# 03_-_SUMOBOT.net
KiCad netlist of a schematic drawn in Altium Designer
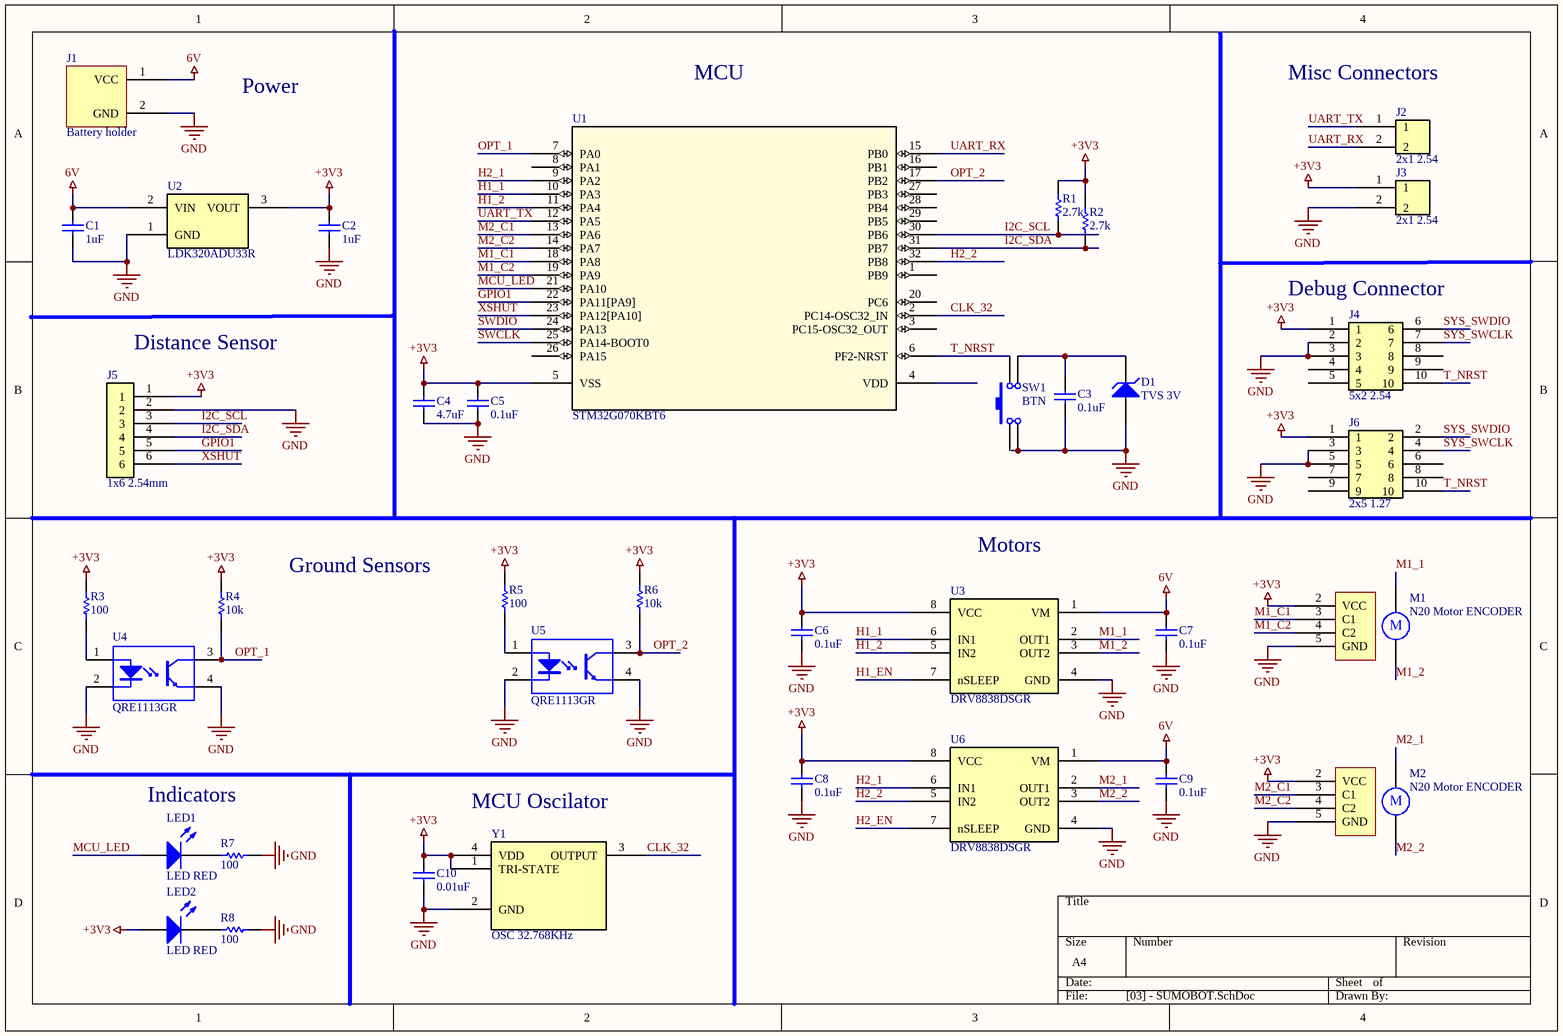
[diagram p0: [03] - SUMOBOT.SchDoc]

(export (version "E")
  (design (tool "Eeschema 10.0.6"))
  (components
    (comp (ref "C1")
      (value "1uF")
      (footprint "CAPC2012X14N")
      (fields
        (field (name "MANUFACTURER") "Samsung")
        (field (name "MANUFACTURER PART NUMBER") "CL21B105KOFNNNG")
        (field (name "TOLERANCE") "10%")
      )
      (libsource (lib "Sumobot2kl20") (part "CL21B105KOFNNNG"))
    )
    (comp (ref "C2")
      (value "1uF")
      (footprint "CAPC2012X14N")
      (fields
        (field (name "MANUFACTURER") "Samsung")
        (field (name "MANUFACTURER PART NUMBER") "CL21B105KOFNNNG")
        (field (name "TOLERANCE") "10%")
      )
      (libsource (lib "Sumobot2kl20") (part "CL21B105KOFNNNG"))
    )
    (comp (ref "C3")
      (value "0.1uF")
      (footprint "CAPC2012X14N")
      (description "CAP CER 0.1UF 50V Y5V 0805")
      (fields
        (field (name "MANUFACTURER") "Samsung")
        (field (name "MANUFACTURER PART NUMBER") "CL21F104ZBCNNNC")
      )
      (libsource (lib "Sumobot2kl20") (part "CL21F104ZBCNNNC"))
    )
    (comp (ref "C4")
      (value "4.7uF")
      (footprint "CAPC2012X14N")
      (fields
        (field (name "MANUFACTURER") "Samsung")
        (field (name "MANUFACTURER PART NUMBER") "CL21B475KOFNNNE")
        (field (name "TOLERANCE") "10%")
      )
      (libsource (lib "Sumobot2kl20") (part "CL21B475KOFNNNE"))
    )
    (comp (ref "C5")
      (value "0.1uF")
      (footprint "CAPC2012X14N")
      (description "CAP CER 0.1UF 50V Y5V 0805")
      (fields
        (field (name "MANUFACTURER") "Samsung")
        (field (name "MANUFACTURER PART NUMBER") "CL21F104ZBCNNNC")
      )
      (libsource (lib "Sumobot2kl20") (part "CL21F104ZBCNNNC"))
    )
    (comp (ref "C6")
      (value "0.1uF")
      (footprint "CAPC2012X14N")
      (description "CAP CER 0.1UF 50V Y5V 0805")
      (fields
        (field (name "MANUFACTURER") "Samsung")
        (field (name "MANUFACTURER PART NUMBER") "CL21F104ZBCNNNC")
      )
      (libsource (lib "Sumobot2kl20") (part "CL21F104ZBCNNNC"))
    )
    (comp (ref "C7")
      (value "0.1uF")
      (footprint "CAPC2012X14N")
      (description "CAP CER 0.1UF 50V Y5V 0805")
      (fields
        (field (name "MANUFACTURER") "Samsung")
        (field (name "MANUFACTURER PART NUMBER") "CL21F104ZBCNNNC")
      )
      (libsource (lib "Sumobot2kl20") (part "CL21F104ZBCNNNC"))
    )
    (comp (ref "C8")
      (value "0.1uF")
      (footprint "CAPC2012X14N")
      (description "CAP CER 0.1UF 50V Y5V 0805")
      (fields
        (field (name "MANUFACTURER") "Samsung")
        (field (name "MANUFACTURER PART NUMBER") "CL21F104ZBCNNNC")
      )
      (libsource (lib "Sumobot2kl20") (part "CL21F104ZBCNNNC"))
    )
    (comp (ref "C9")
      (value "0.1uF")
      (footprint "CAPC2012X14N")
      (description "CAP CER 0.1UF 50V Y5V 0805")
      (fields
        (field (name "MANUFACTURER") "Samsung")
        (field (name "MANUFACTURER PART NUMBER") "CL21F104ZBCNNNC")
      )
      (libsource (lib "Sumobot2kl20") (part "CL21F104ZBCNNNC"))
    )
    (comp (ref "C10")
      (value "0.01uF")
      (footprint "CAPC2012X14N")
      (fields
        (field (name "MANUFACTURER") "Samsung")
        (field (name "MANUFACTURER PART NUMBER") "CL21B103KBANNNC")
        (field (name "TOLERANCE") "10%")
      )
      (libsource (lib "Sumobot2kl20") (part "CL21B103KBANNNC"))
    )
    (comp (ref "D1")
      (value "TVS 3V")
      (footprint "ST0201")
      (description "ESD Suppressor TVS 8KV 2-Pin SMD T/R")
      (fields
        (field (name "MANUFACTURER") "STMicroelectronics")
        (field (name "MANUFACTURER PART NUMBER") "ESDALC6V1-1U2")
      )
      (libsource (lib "Sumobot2kl20") (part "ESDALC6V1-1U2"))
    )
    (comp (ref "J1")
      (value "Battery holder")
      (footprint "Battery Holder")
      (libsource (lib "Sumobot2kl20") (part "Battery holder"))
    )
    (comp (ref "J2")
      (value "2x1 2.54")
      (footprint "2 2.54")
      (description "CONN HEADER VERT 2POS 2.54MM")
      (fields
        (field (name "MANUFACTURER") "Sullins")
        (field (name "MANUFACTURER PART NUMBER") "PREC002SAAN-RC")
      )
      (libsource (lib "Sumobot2kl20") (part "PREC002SAAN-RC"))
    )
    (comp (ref "J3")
      (value "2x1 2.54")
      (footprint "2 2.54")
      (description "CONN HEADER VERT 2POS 2.54MM")
      (fields
        (field (name "MANUFACTURER") "Sullins")
        (field (name "MANUFACTURER PART NUMBER") "PREC002SAAN-RC")
      )
      (libsource (lib "Sumobot2kl20") (part "PREC002SAAN-RC"))
    )
    (comp (ref "J4")
      (value "5x2 2.54")
      (footprint "5x2 2.54")
      (description "Conn Unshrouded Header HDR 80 POS 2.54mm Solder RA Thru-Hole Bag")
      (fields
        (field (name "MANUFACTURER") "Adam Equipment")
        (field (name "MANUFACTURER PART NUMBER") "PH2-10-UA")
      )
      (libsource (lib "Sumobot2kl20") (part "PH2-10-UA"))
    )
    (comp (ref "J5")
      (value "1x6 2.54mm")
      (footprint "PIN 6x1 2.54mm")
      (description "Conn Unshrouded Header HDR 6 POS 2.54mm Solder RA Thru-Hole")
      (fields
        (field (name "MANUFACTURER") "Adam Equipment")
        (field (name "MANUFACTURER PART NUMBER") "PH1RA-06-UA")
      )
      (libsource (lib "Sumobot2kl20") (part "PH1RA-06-UA"))
    )
    (comp (ref "J6")
      (value "2x5 1.27")
      (footprint "5x2 1.27")
      (description "CONN HEADER VERT 10POS 1.27MM")
      (fields
        (field (name "MANUFACTURER") "CNC Tech")
        (field (name "MANUFACTURER PART NUMBER") "3220-10-0100-00")
      )
      (libsource (lib "Sumobot2kl20") (part "3220-10-0100-00"))
    )
    (comp (ref "LED1")
      (value "LED RED")
      (footprint "LED 0805")
      (description "SMD LED red 2.4 V 0805, 150080RS75000, Würth Elektronik")
      (fields
        (field (name "MANUFACTURER") "Wurth Electronics")
        (field (name "MANUFACTURER PART NUMBER") "150080RS75000")
      )
      (libsource (lib "Sumobot2kl20") (part "150080RS75000"))
    )
    (comp (ref "LED2")
      (value "LED RED")
      (footprint "LED 0805")
      (description "SMD LED red 2.4 V 0805, 150080RS75000, Würth Elektronik")
      (fields
        (field (name "MANUFACTURER") "Wurth Electronics")
        (field (name "MANUFACTURER PART NUMBER") "150080RS75000")
      )
      (libsource (lib "Sumobot2kl20") (part "150080RS75000"))
    )
    (comp (ref "M1")
      (value "N20 Motor ENCODER")
      (footprint "N20 MOTOR - ENCODER")
      (libsource (lib "Sumobot2kl20") (part "N20 Motor ENCODER"))
    )
    (comp (ref "M2")
      (value "N20 Motor ENCODER")
      (footprint "N20 MOTOR - ENCODER")
      (libsource (lib "Sumobot2kl20") (part "N20 Motor ENCODER"))
    )
    (comp (ref "R1")
      (value "2.7k")
      (footprint "RESC2012X07N")
      (description "Res Thick Film 0805 2.7K Ohm 1% 0.125W(1/8W) ±100ppm/C Pad SMD Automotive T/R")
      (fields
        (field (name "MANUFACTURER") "Panasonic")
        (field (name "MANUFACTURER PART NUMBER") "ERJ-6ENF2701V")
      )
      (libsource (lib "Sumobot2kl20") (part "ERJ-6ENF2701V"))
    )
    (comp (ref "R2")
      (value "2.7k")
      (footprint "RESC2012X07N")
      (description "Res Thick Film 0805 2.7K Ohm 1% 0.125W(1/8W) ±100ppm/C Pad SMD Automotive T/R")
      (fields
        (field (name "MANUFACTURER") "Panasonic")
        (field (name "MANUFACTURER PART NUMBER") "ERJ-6ENF2701V")
      )
      (libsource (lib "Sumobot2kl20") (part "ERJ-6ENF2701V"))
    )
    (comp (ref "R3")
      (value "100")
      (footprint "RESC2012X07N")
      (description "PANASONIC - ERJ6ENF1000V - DICKSCH.WIDERSTAND 100R 1% 0.125W 0805")
      (fields
        (field (name "MANUFACTURER") "Panasonic")
        (field (name "MANUFACTURER PART NUMBER") "ERJ-6ENF1000V")
      )
      (libsource (lib "Sumobot2kl20") (part "ERJ-6ENF1000V"))
    )
    (comp (ref "R4")
      (value "10k")
      (footprint "RESC2012X07N")
      (fields
        (field (name "MANUFACTURER") "Panasonic")
        (field (name "MANUFACTURER PART NUMBER") "ERJ-6ENF1002V")
        (field (name "TOLERANCE") "1%")
      )
      (libsource (lib "Sumobot2kl20") (part "ERJ-6ENF1002V"))
    )
    (comp (ref "R5")
      (value "100")
      (footprint "RESC2012X07N")
      (description "PANASONIC - ERJ6ENF1000V - DICKSCH.WIDERSTAND 100R 1% 0.125W 0805")
      (fields
        (field (name "MANUFACTURER") "Panasonic")
        (field (name "MANUFACTURER PART NUMBER") "ERJ-6ENF1000V")
      )
      (libsource (lib "Sumobot2kl20") (part "ERJ-6ENF1000V"))
    )
    (comp (ref "R6")
      (value "10k")
      (footprint "RESC2012X07N")
      (fields
        (field (name "MANUFACTURER") "Panasonic")
        (field (name "MANUFACTURER PART NUMBER") "ERJ-6ENF1002V")
        (field (name "TOLERANCE") "1%")
      )
      (libsource (lib "Sumobot2kl20") (part "ERJ-6ENF1002V"))
    )
    (comp (ref "R7")
      (value "100")
      (footprint "RESC2012X07N")
      (description "PANASONIC - ERJ6ENF1000V - DICKSCH.WIDERSTAND 100R 1% 0.125W 0805")
      (fields
        (field (name "MANUFACTURER") "Panasonic")
        (field (name "MANUFACTURER PART NUMBER") "ERJ-6ENF1000V")
      )
      (libsource (lib "Sumobot2kl20") (part "ERJ-6ENF1000V"))
    )
    (comp (ref "R8")
      (value "100")
      (footprint "RESC2012X07N")
      (description "PANASONIC - ERJ6ENF1000V - DICKSCH.WIDERSTAND 100R 1% 0.125W 0805")
      (fields
        (field (name "MANUFACTURER") "Panasonic")
        (field (name "MANUFACTURER PART NUMBER") "ERJ-6ENF1000V")
      )
      (libsource (lib "Sumobot2kl20") (part "ERJ-6ENF1000V"))
    )
    (comp (ref "SW1")
      (value "BTN")
      (footprint "Button")
      (description "INWALL LENS COVER , WHITE , 6 (")
      (fields
        (field (name "MANUFACTURER") "ITT C&K")
        (field (name "MANUFACTURER PART NUMBER") "PTS647SK70SMTR2LFS")
      )
      (libsource (lib "Sumobot2kl20") (part "PTS647SK70SMTR2LFS"))
    )
    (comp (ref "U1")
      (value "STM32G070KBT6")
      (footprint "LQFP-32")
      (description "Cortex M0+ 128K LQFP32 85°C")
      (fields (field (name "MANUFACTURER") "STMicroelectronics"))
      (libsource (lib "Sumobot2kl20") (part "STM32G070KBT6"))
    )
    (comp (ref "U2")
      (value "LDK320ADU33R")
      (footprint "SOT89-150P349X160-3N")
      (description "LDO Regulator Pos 3.3V 0.2A 4-Pin(3+Tab) SOT-89 T/R")
      (fields (field (name "MANUFACTURER") "STMicroelectronics"))
      (libsource (lib "Sumobot2kl20") (part "LDK320ADU33R"))
    )
    (comp (ref "U3")
      (value "DRV8838DSGR")
      (footprint "SON50P200X80_HS-9N2")
      (fields (field (name "MANUFACTURER") "Texas Instruments"))
      (libsource (lib "Sumobot2kl20") (part "DRV8838DSGR"))
    )
    (comp (ref "U4")
      (value "QRE1113GR")
      (footprint "FAIR-QRE1113GR_V")
      (description "Photointerrupter Reflective Phototransistor 4-Pin Miniature SMT T/R")
      (fields (field (name "MANUFACTURER") "ON Semiconductor / Fairchild"))
      (libsource (lib "Sumobot2kl20") (part "QRE1113GR"))
    )
    (comp (ref "U5")
      (value "QRE1113GR")
      (footprint "FAIR-QRE1113GR_V")
      (description "Photointerrupter Reflective Phototransistor 4-Pin Miniature SMT T/R")
      (fields (field (name "MANUFACTURER") "ON Semiconductor / Fairchild"))
      (libsource (lib "Sumobot2kl20") (part "QRE1113GR"))
    )
    (comp (ref "U6")
      (value "DRV8838DSGR")
      (footprint "SON50P200X80_HS-9N2")
      (fields (field (name "MANUFACTURER") "Texas Instruments"))
      (libsource (lib "Sumobot2kl20") (part "DRV8838DSGR"))
    )
    (comp (ref "Y1")
      (value "OSC 32.768KHz")
      (footprint "ECS-327MVATX")
      (description "Oscillator XO 0.032768MHz ±25ppm 15pF CMOS 55% 1.8V/2.5V/3.3V 4-Pin Mini-SMD T/R")
      (fields
        (field (name "MANUFACTURER") "ECS International")
        (field (name "MANUFACTURER PART NUMBER") "ECS-327MVATX-3-CN-TR")
      )
      (libsource (lib "Sumobot2kl20") (part "ECS-327MVATX-3-CN-TR"))
    )
  )
  (nets
    (net (code "1") (name "+3V3") (class "Default")
      (node (ref "C10") (pin "2") (pinfunction "2_2") (pintype "passive"))
      (node (ref "C2") (pin "2") (pinfunction "2_2") (pintype "passive"))
      (node (ref "C4") (pin "2") (pinfunction "2_2") (pintype "passive"))
      (node (ref "C5") (pin "2") (pinfunction "2_2") (pintype "passive"))
      (node (ref "C6") (pin "2") (pinfunction "2_2") (pintype "passive"))
      (node (ref "C8") (pin "2") (pinfunction "2_2") (pintype "passive"))
      (node (ref "J3") (pin "1") (pinfunction "1_1") (pintype "passive"))
      (node (ref "J4") (pin "1") (pinfunction "1_1") (pintype "passive"))
      (node (ref "J5") (pin "1") (pinfunction "1_1") (pintype "passive"))
      (node (ref "J6") (pin "1") (pinfunction "1_1") (pintype "passive"))
      (node (ref "LED2") (pin "1") (pinfunction "A_1") (pintype "passive"))
      (node (ref "M1") (pin "2") (pinfunction "VCC_2") (pintype "passive"))
      (node (ref "M2") (pin "2") (pinfunction "VCC_2") (pintype "passive"))
      (node (ref "R1") (pin "2") (pinfunction "2_2") (pintype "passive"))
      (node (ref "R2") (pin "2") (pinfunction "2_2") (pintype "passive"))
      (node (ref "R3") (pin "2") (pinfunction "2_2") (pintype "passive"))
      (node (ref "R4") (pin "2") (pinfunction "2_2") (pintype "passive"))
      (node (ref "R5") (pin "2") (pinfunction "2_2") (pintype "passive"))
      (node (ref "R6") (pin "2") (pinfunction "2_2") (pintype "passive"))
      (node (ref "U1") (pin "5") (pinfunction "VSS_5") (pintype "power_in"))
      (node (ref "U2") (pin "3") (pinfunction "VOUT_3") (pintype "passive"))
      (node (ref "U3") (pin "8") (pinfunction "VCC_8") (pintype "passive"))
      (node (ref "U6") (pin "8") (pinfunction "VCC_8") (pintype "passive"))
      (node (ref "Y1") (pin "1") (pinfunction "TRI-STATE_1") (pintype "passive"))
      (node (ref "Y1") (pin "4") (pinfunction "VDD_4") (pintype "passive"))
    )
    (net (code "2") (name "/CLK_32") (class "Default")
      (node (ref "U1") (pin "2") (pinfunction "PC14-OSC32_IN_2") (pintype "bidirectional"))
      (node (ref "Y1") (pin "3") (pinfunction "OUTPUT_3") (pintype "passive"))
    )
    (net (code "3") (name "/GPIO1") (class "Default")
      (node (ref "J5") (pin "5") (pinfunction "5_5") (pintype "passive"))
      (node (ref "U1") (pin "22") (pinfunction "PA11[PA9]_22") (pintype "bidirectional"))
    )
    (net (code "4") (name "/H1_1") (class "Default")
      (node (ref "U1") (pin "10") (pinfunction "PA3_10") (pintype "bidirectional"))
      (node (ref "U3") (pin "6") (pinfunction "IN1_6") (pintype "passive"))
    )
    (net (code "5") (name "/H1_2") (class "Default")
      (node (ref "U1") (pin "11") (pinfunction "PA4_11") (pintype "bidirectional"))
      (node (ref "U3") (pin "5") (pinfunction "IN2_5") (pintype "passive"))
    )
    (net (code "6") (name "/H1_EN") (class "Default")
      (node (ref "U3") (pin "7") (pinfunction "nSLEEP_7") (pintype "passive"))
    )
    (net (code "7") (name "/H2_1") (class "Default")
      (node (ref "U1") (pin "9") (pinfunction "PA2_9") (pintype "bidirectional"))
      (node (ref "U6") (pin "6") (pinfunction "IN1_6") (pintype "passive"))
    )
    (net (code "8") (name "/H2_2") (class "Default")
      (node (ref "U1") (pin "32") (pinfunction "PB8_32") (pintype "bidirectional"))
      (node (ref "U6") (pin "5") (pinfunction "IN2_5") (pintype "passive"))
    )
    (net (code "9") (name "/H2_EN") (class "Default")
      (node (ref "U6") (pin "7") (pinfunction "nSLEEP_7") (pintype "passive"))
    )
    (net (code "10") (name "/I2C_SCL") (class "Default")
      (node (ref "J5") (pin "3") (pinfunction "3_3") (pintype "passive"))
      (node (ref "R1") (pin "1") (pinfunction "1_1") (pintype "passive"))
      (node (ref "U1") (pin "30") (pinfunction "PB6_30") (pintype "bidirectional"))
    )
    (net (code "11") (name "/I2C_SDA") (class "Default")
      (node (ref "J5") (pin "4") (pinfunction "4_4") (pintype "passive"))
      (node (ref "R2") (pin "1") (pinfunction "1_1") (pintype "passive"))
      (node (ref "U1") (pin "31") (pinfunction "PB7_31") (pintype "bidirectional"))
    )
    (net (code "12") (name "/M1_1") (class "Default")
      (node (ref "M1") (pin "1") (pinfunction "1_1") (pintype "passive"))
      (node (ref "U3") (pin "2") (pinfunction "OUT1_2") (pintype "passive"))
    )
    (net (code "13") (name "/M1_2") (class "Default")
      (node (ref "M1") (pin "6") (pinfunction "2_6") (pintype "passive"))
      (node (ref "U3") (pin "3") (pinfunction "OUT2_3") (pintype "passive"))
    )
    (net (code "14") (name "/M1_C1") (class "Default")
      (node (ref "M1") (pin "3") (pinfunction "C1_3") (pintype "passive"))
      (node (ref "U1") (pin "18") (pinfunction "PA8_18") (pintype "bidirectional"))
    )
    (net (code "15") (name "/M1_C2") (class "Default")
      (node (ref "M1") (pin "4") (pinfunction "C2_4") (pintype "passive"))
      (node (ref "U1") (pin "19") (pinfunction "PA9_19") (pintype "bidirectional"))
    )
    (net (code "16") (name "/M2_1") (class "Default")
      (node (ref "M2") (pin "1") (pinfunction "1_1") (pintype "passive"))
      (node (ref "U6") (pin "2") (pinfunction "OUT1_2") (pintype "passive"))
    )
    (net (code "17") (name "/M2_2") (class "Default")
      (node (ref "M2") (pin "6") (pinfunction "2_6") (pintype "passive"))
      (node (ref "U6") (pin "3") (pinfunction "OUT2_3") (pintype "passive"))
    )
    (net (code "18") (name "/M2_C1") (class "Default")
      (node (ref "M2") (pin "3") (pinfunction "C1_3") (pintype "passive"))
      (node (ref "U1") (pin "13") (pinfunction "PA6_13") (pintype "bidirectional"))
    )
    (net (code "19") (name "/M2_C2") (class "Default")
      (node (ref "M2") (pin "4") (pinfunction "C2_4") (pintype "passive"))
      (node (ref "U1") (pin "14") (pinfunction "PA7_14") (pintype "bidirectional"))
    )
    (net (code "20") (name "/MCU_LED") (class "Default")
      (node (ref "LED1") (pin "1") (pinfunction "A_1") (pintype "passive"))
      (node (ref "U1") (pin "21") (pinfunction "PA10_21") (pintype "bidirectional"))
    )
    (net (code "21") (name "/OPT_1") (class "Default")
      (node (ref "R4") (pin "1") (pinfunction "1_1") (pintype "passive"))
      (node (ref "U1") (pin "7") (pinfunction "PA0_7") (pintype "bidirectional"))
      (node (ref "U4") (pin "3") (pinfunction "COLLECTOR_3") (pintype "passive"))
    )
    (net (code "22") (name "/OPT_2") (class "Default")
      (node (ref "R6") (pin "1") (pinfunction "1_1") (pintype "passive"))
      (node (ref "U1") (pin "17") (pinfunction "PB2_17") (pintype "bidirectional"))
      (node (ref "U5") (pin "3") (pinfunction "COLLECTOR_3") (pintype "passive"))
    )
    (net (code "23") (name "/SWCLK") (class "Default")
      (node (ref "U1") (pin "25") (pinfunction "PA14-BOOT0_25") (pintype "bidirectional"))
    )
    (net (code "24") (name "/SWDIO") (class "Default")
      (node (ref "U1") (pin "24") (pinfunction "PA13_24") (pintype "bidirectional"))
    )
    (net (code "25") (name "/SYS_SWCLK") (class "Default")
      (node (ref "J4") (pin "7") (pinfunction "7_7") (pintype "passive"))
      (node (ref "J6") (pin "4") (pinfunction "4_4") (pintype "passive"))
    )
    (net (code "26") (name "/SYS_SWDIO") (class "Default")
      (node (ref "J4") (pin "6") (pinfunction "6_6") (pintype "passive"))
      (node (ref "J6") (pin "2") (pinfunction "2_2") (pintype "passive"))
    )
    (net (code "27") (name "/T_NRST") (class "Default")
      (node (ref "J4") (pin "10") (pinfunction "10_10") (pintype "passive"))
      (node (ref "J6") (pin "10") (pinfunction "10_10") (pintype "passive"))
      (node (ref "SW1") (pin "3") (pinfunction "2_3") (pintype "passive"))
      (node (ref "U1") (pin "6") (pinfunction "PF2-NRST_6") (pintype "bidirectional"))
    )
    (net (code "28") (name "/UART_RX") (class "Default")
      (node (ref "J2") (pin "2") (pinfunction "2_2") (pintype "passive"))
      (node (ref "U1") (pin "15") (pinfunction "PB0_15") (pintype "bidirectional"))
    )
    (net (code "29") (name "/UART_TX") (class "Default")
      (node (ref "J2") (pin "1") (pinfunction "1_1") (pintype "passive"))
      (node (ref "U1") (pin "12") (pinfunction "PA5_12") (pintype "bidirectional"))
    )
    (net (code "30") (name "/XSHUT") (class "Default")
      (node (ref "J5") (pin "6") (pinfunction "6_6") (pintype "passive"))
      (node (ref "U1") (pin "23") (pinfunction "PA12[PA10]_23") (pintype "bidirectional"))
    )
    (net (code "31") (name "6V") (class "Default")
      (node (ref "C1") (pin "2") (pinfunction "2_2") (pintype "passive"))
      (node (ref "C7") (pin "2") (pinfunction "2_2") (pintype "passive"))
      (node (ref "C9") (pin "2") (pinfunction "2_2") (pintype "passive"))
      (node (ref "J1") (pin "1") (pinfunction "VCC_1") (pintype "passive"))
      (node (ref "U2") (pin "2") (pinfunction "VIN_2") (pintype "passive"))
      (node (ref "U3") (pin "1") (pinfunction "VM_1") (pintype "passive"))
      (node (ref "U6") (pin "1") (pinfunction "VM_1") (pintype "passive"))
    )
    (net (code "32") (name "GND") (class "Default")
      (node (ref "C1") (pin "1") (pinfunction "1_1") (pintype "passive"))
      (node (ref "C10") (pin "1") (pinfunction "1_1") (pintype "passive"))
      (node (ref "C2") (pin "1") (pinfunction "1_1") (pintype "passive"))
      (node (ref "C3") (pin "1") (pinfunction "1_1") (pintype "passive"))
      (node (ref "C4") (pin "1") (pinfunction "1_1") (pintype "passive"))
      (node (ref "C5") (pin "1") (pinfunction "1_1") (pintype "passive"))
      (node (ref "C6") (pin "1") (pinfunction "1_1") (pintype "passive"))
      (node (ref "C7") (pin "1") (pinfunction "1_1") (pintype "passive"))
      (node (ref "C8") (pin "1") (pinfunction "1_1") (pintype "passive"))
      (node (ref "C9") (pin "1") (pinfunction "1_1") (pintype "passive"))
      (node (ref "D1") (pin "2") (pinfunction "A_2") (pintype "passive"))
      (node (ref "J1") (pin "2") (pinfunction "GND_2") (pintype "passive"))
      (node (ref "J3") (pin "2") (pinfunction "2_2") (pintype "passive"))
      (node (ref "J4") (pin "2") (pinfunction "2_2") (pintype "passive"))
      (node (ref "J4") (pin "3") (pinfunction "3_3") (pintype "passive"))
      (node (ref "J5") (pin "2") (pinfunction "2_2") (pintype "passive"))
      (node (ref "J6") (pin "3") (pinfunction "3_3") (pintype "passive"))
      (node (ref "J6") (pin "5") (pinfunction "5_5") (pintype "passive"))
      (node (ref "M1") (pin "5") (pinfunction "GND_5") (pintype "passive"))
      (node (ref "M2") (pin "5") (pinfunction "GND_5") (pintype "passive"))
      (node (ref "R7") (pin "1") (pinfunction "1_1") (pintype "passive"))
      (node (ref "R8") (pin "1") (pinfunction "1_1") (pintype "passive"))
      (node (ref "SW1") (pin "2") (pinfunction "1_2") (pintype "passive"))
      (node (ref "U2") (pin "1") (pinfunction "GND_1") (pintype "passive"))
      (node (ref "U3") (pin "4") (pinfunction "GND_4") (pintype "passive"))
      (node (ref "U4") (pin "2") (pinfunction "CATHODE_2") (pintype "passive"))
      (node (ref "U4") (pin "4") (pinfunction "EMITTER_4") (pintype "passive"))
      (node (ref "U5") (pin "2") (pinfunction "CATHODE_2") (pintype "passive"))
      (node (ref "U5") (pin "4") (pinfunction "EMITTER_4") (pintype "passive"))
      (node (ref "U6") (pin "4") (pinfunction "GND_4") (pintype "passive"))
      (node (ref "Y1") (pin "2") (pinfunction "GND_2") (pintype "passive"))
    )
    (net (code "33") (name "Net-(D1-K)") (class "Default")
      (node (ref "C3") (pin "2") (pinfunction "2_2") (pintype "passive"))
      (node (ref "D1") (pin "1") (pinfunction "K_1") (pintype "passive"))
      (node (ref "SW1") (pin "4") (pinfunction "3_4") (pintype "passive"))
    )
    (net (code "34") (name "Net-(LED1-K)") (class "Default")
      (node (ref "LED1") (pin "2") (pinfunction "K_2") (pintype "passive"))
      (node (ref "R7") (pin "2") (pinfunction "2_2") (pintype "passive"))
    )
    (net (code "35") (name "Net-(LED2-K)") (class "Default")
      (node (ref "LED2") (pin "2") (pinfunction "K_2") (pintype "passive"))
      (node (ref "R8") (pin "2") (pinfunction "2_2") (pintype "passive"))
    )
    (net (code "36") (name "Net-(U4-ANODE)") (class "Default")
      (node (ref "R3") (pin "1") (pinfunction "1_1") (pintype "passive"))
      (node (ref "U4") (pin "1") (pinfunction "ANODE_1") (pintype "passive"))
    )
    (net (code "37") (name "Net-(U5-ANODE)") (class "Default")
      (node (ref "R5") (pin "1") (pinfunction "1_1") (pintype "passive"))
      (node (ref "U5") (pin "1") (pinfunction "ANODE_1") (pintype "passive"))
    )
    (net (code "38") (name "unconnected-(J4-Pad4)") (class "Default")
      (node (ref "J4") (pin "4") (pinfunction "4_4") (pintype "passive"))
    )
    (net (code "39") (name "unconnected-(J4-Pad5)") (class "Default")
      (node (ref "J4") (pin "5") (pinfunction "5_5") (pintype "passive"))
    )
    (net (code "40") (name "unconnected-(J4-Pad8)") (class "Default")
      (node (ref "J4") (pin "8") (pinfunction "8_8") (pintype "passive"))
    )
    (net (code "41") (name "unconnected-(J4-Pad9)") (class "Default")
      (node (ref "J4") (pin "9") (pinfunction "9_9") (pintype "passive"))
    )
    (net (code "42") (name "unconnected-(J6-Pad6)") (class "Default")
      (node (ref "J6") (pin "6") (pinfunction "6_6") (pintype "passive"))
    )
    (net (code "43") (name "unconnected-(J6-Pad7)") (class "Default")
      (node (ref "J6") (pin "7") (pinfunction "7_7") (pintype "passive"))
    )
    (net (code "44") (name "unconnected-(J6-Pad8)") (class "Default")
      (node (ref "J6") (pin "8") (pinfunction "8_8") (pintype "passive"))
    )
    (net (code "45") (name "unconnected-(J6-Pad9)") (class "Default")
      (node (ref "J6") (pin "9") (pinfunction "9_9") (pintype "passive"))
    )
    (net (code "46") (name "unconnected-(SW1-Pad1)") (class "Default")
      (node (ref "SW1") (pin "1") (pinfunction "1_1") (pintype "passive"))
    )
    (net (code "47") (name "unconnected-(U1-PA1-Pad8)") (class "Default")
      (node (ref "U1") (pin "8") (pinfunction "PA1_8") (pintype "bidirectional"))
    )
    (net (code "48") (name "unconnected-(U1-PA15-Pad26)") (class "Default")
      (node (ref "U1") (pin "26") (pinfunction "PA15_26") (pintype "bidirectional"))
    )
    (net (code "49") (name "unconnected-(U1-PB1-Pad16)") (class "Default")
      (node (ref "U1") (pin "16") (pinfunction "PB1_16") (pintype "bidirectional"))
    )
    (net (code "50") (name "unconnected-(U1-PB3-Pad27)") (class "Default")
      (node (ref "U1") (pin "27") (pinfunction "PB3_27") (pintype "bidirectional"))
    )
    (net (code "51") (name "unconnected-(U1-PB4-Pad28)") (class "Default")
      (node (ref "U1") (pin "28") (pinfunction "PB4_28") (pintype "bidirectional"))
    )
    (net (code "52") (name "unconnected-(U1-PB5-Pad29)") (class "Default")
      (node (ref "U1") (pin "29") (pinfunction "PB5_29") (pintype "bidirectional"))
    )
    (net (code "53") (name "unconnected-(U1-PB9-Pad1)") (class "Default")
      (node (ref "U1") (pin "1") (pinfunction "PB9_1") (pintype "bidirectional"))
    )
    (net (code "54") (name "unconnected-(U1-PC6-Pad20)") (class "Default")
      (node (ref "U1") (pin "20") (pinfunction "PC6_20") (pintype "bidirectional"))
    )
    (net (code "55") (name "unconnected-(U1-PC15-OSC32_OUT-Pad3)") (class "Default")
      (node (ref "U1") (pin "3") (pinfunction "PC15-OSC32_OUT_3") (pintype "bidirectional"))
    )
    (net (code "56") (name "unconnected-(U1-VDD-Pad4)") (class "Default")
      (node (ref "U1") (pin "4") (pinfunction "VDD_4") (pintype "power_in"))
    )
  )
)
